# SCH_miniEsp_2025-01-17.net
KiCad netlist of a schematic drawn in EasyEDA
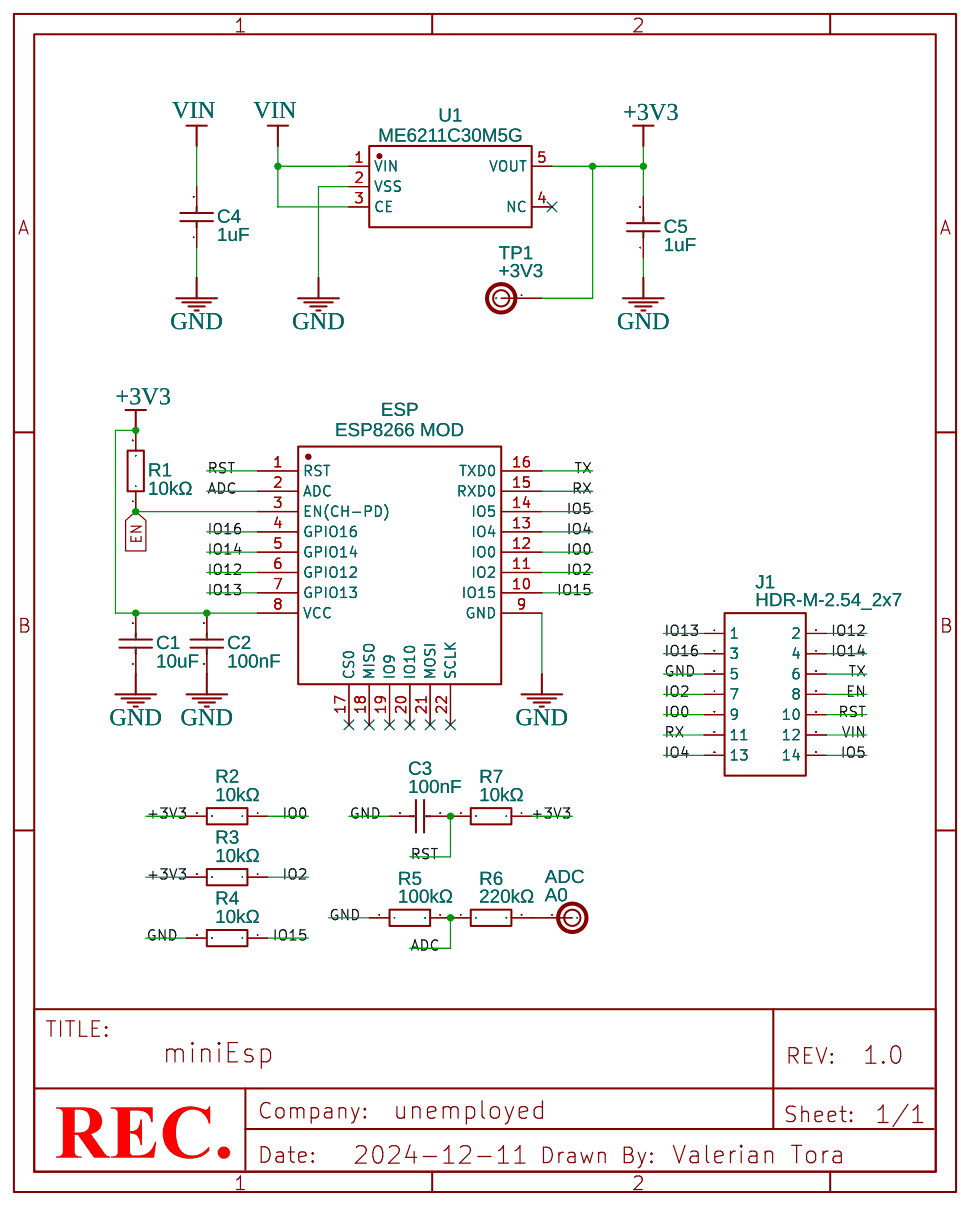
[diagram p0: schematic sheet]

(export (version "E")
  (design (tool "Eeschema 10.0.6"))
  (components
    (comp (ref "ADC") (value "A0") (libsource (lib "") (part "Test Point")))
    (comp (ref "C1")
      (value "10uF")
      (fields
        (field (name "Manufacturer Part") "CL21A106KPFNNNE")
        (field (name "Manufacturer") "SAMSUNG(三星)")
      )
      (libsource (lib "") (part "CL21A106KPFNNNE"))
    )
    (comp (ref "C2")
      (value "100nF")
      (fields
        (field (name "Manufacturer Part") "CL21B104KBCNNNC")
        (field (name "Manufacturer") "SAMSUNG(三星)")
      )
      (libsource (lib "") (part "CL21B104KBCNNNC"))
    )
    (comp (ref "C3")
      (value "100nF")
      (fields
        (field (name "Manufacturer Part") "CL21B104KBCNNNC")
        (field (name "Manufacturer") "SAMSUNG(三星)")
      )
      (libsource (lib "") (part "CL21B104KBCNNNC_1"))
    )
    (comp (ref "C4")
      (value "1uF")
      (fields
        (field (name "Manufacturer Part") "CL21B105KBFNNNE")
        (field (name "Manufacturer") "SAMSUNG(三星)")
      )
      (libsource (lib "") (part "CL21B105KBFNNNE"))
    )
    (comp (ref "C5")
      (value "1uF")
      (fields
        (field (name "Manufacturer Part") "CL21B105KBFNNNE")
        (field (name "Manufacturer") "SAMSUNG(三星)")
      )
      (libsource (lib "") (part "CL21B105KBFNNNE"))
    )
    (comp (ref "ESP")
      (value "ESP8266 MOD")
      (fields
        (field (name "Manufacturer Part") "ESP-12F(ESP8266MOD)")
        (field (name "Manufacturer") "Ai-Thinker(安信可)")
      )
      (libsource (lib "") (part "ESP8266 12F"))
    )
    (comp (ref "J1") (value "HDR-M-2.54_2x7") (libsource (lib "") (part "HDR-M-2.54_2x7")))
    (comp (ref "R1")
      (value "10kΩ")
      (fields (field (name "Manufacturer Part") "AC0603FR-0710KL") (field (name "Manufacturer") "YAGEO(国巨)"))
      (libsource (lib "") (part "AC0603FR-0710KL_1"))
    )
    (comp (ref "R2")
      (value "10kΩ")
      (fields (field (name "Manufacturer Part") "AC0603FR-0710KL") (field (name "Manufacturer") "YAGEO(国巨)"))
      (libsource (lib "") (part "AC0603FR-0710KL"))
    )
    (comp (ref "R3")
      (value "10kΩ")
      (fields (field (name "Manufacturer Part") "AC0603FR-0710KL") (field (name "Manufacturer") "YAGEO(国巨)"))
      (libsource (lib "") (part "AC0603FR-0710KL"))
    )
    (comp (ref "R4")
      (value "10kΩ")
      (fields (field (name "Manufacturer Part") "AC0603FR-0710KL") (field (name "Manufacturer") "YAGEO(国巨)"))
      (libsource (lib "") (part "AC0603FR-0710KL"))
    )
    (comp (ref "R5")
      (value "100kΩ")
      (fields (field (name "Manufacturer Part") "RC0603FR-07100KL") (field (name "Manufacturer") "YAGEO(国巨)"))
      (libsource (lib "") (part "RC0603FR-07100KL"))
    )
    (comp (ref "R6")
      (value "220kΩ")
      (fields (field (name "Manufacturer Part") "RC0603FR-07220KL") (field (name "Manufacturer") "YAGEO(国巨)"))
      (libsource (lib "") (part "RC0603FR-07220KL"))
    )
    (comp (ref "R7")
      (value "10kΩ")
      (fields (field (name "Manufacturer Part") "AC0603FR-0710KL") (field (name "Manufacturer") "YAGEO(国巨)"))
      (libsource (lib "") (part "AC0603FR-0710KL"))
    )
    (comp (ref "TP1") (value "+3V3") (libsource (lib "") (part "Test Point_1")))
    (comp (ref "U1")
      (value "ME6211C30M5G")
      (fields (field (name "Manufacturer") "MICRONE(南京微盟)"))
      (libsource (lib "") (part "ME6211C30M5G"))
    )
  )
  (nets
    (net (code "1") (name "+3V3") (class "Default")
      (node (ref "C1") (pin "2") (pinfunction "2_2") (pintype "input"))
      (node (ref "C2") (pin "2") (pinfunction "2_2") (pintype "input"))
      (node (ref "C5") (pin "2") (pinfunction "2_2") (pintype "input"))
      (node (ref "ESP") (pin "8") (pinfunction "VCC_8") (pintype "unspecified"))
      (node (ref "R1") (pin "2") (pinfunction "2_2") (pintype "input"))
      (node (ref "R2") (pin "2") (pinfunction "2_2") (pintype "input"))
      (node (ref "R3") (pin "2") (pinfunction "2_2") (pintype "input"))
      (node (ref "R7") (pin "1") (pinfunction "1_1") (pintype "input"))
      (node (ref "TP1") (pin "1") (pinfunction "1_1") (pintype "output"))
      (node (ref "U1") (pin "5") (pinfunction "VOUT_5") (pintype "unspecified"))
    )
    (net (code "2") (name "/ADC") (class "Default")
      (node (ref "ESP") (pin "2") (pinfunction "ADC_2") (pintype "unspecified"))
      (node (ref "R5") (pin "2") (pinfunction "2_2") (pintype "unspecified"))
      (node (ref "R6") (pin "1") (pinfunction "1_1") (pintype "input"))
    )
    (net (code "3") (name "/IO0") (class "Default")
      (node (ref "ESP") (pin "12") (pinfunction "IO0_12") (pintype "unspecified"))
      (node (ref "J1") (pin "9") (pinfunction "9_9") (pintype "input"))
      (node (ref "R2") (pin "1") (pinfunction "1_1") (pintype "input"))
    )
    (net (code "4") (name "/IO2") (class "Default")
      (node (ref "ESP") (pin "11") (pinfunction "IO2_11") (pintype "unspecified"))
      (node (ref "J1") (pin "7") (pinfunction "7_7") (pintype "input"))
      (node (ref "R3") (pin "1") (pinfunction "1_1") (pintype "input"))
    )
    (net (code "5") (name "/IO4") (class "Default")
      (node (ref "ESP") (pin "13") (pinfunction "IO4_13") (pintype "unspecified"))
      (node (ref "J1") (pin "13") (pinfunction "13_13") (pintype "input"))
    )
    (net (code "6") (name "/IO5") (class "Default")
      (node (ref "ESP") (pin "14") (pinfunction "IO5_14") (pintype "unspecified"))
      (node (ref "J1") (pin "14") (pinfunction "14_14") (pintype "input"))
    )
    (net (code "7") (name "/IO12") (class "Default")
      (node (ref "ESP") (pin "6") (pinfunction "GPIO12_6") (pintype "unspecified"))
      (node (ref "J1") (pin "2") (pinfunction "2_2") (pintype "input"))
    )
    (net (code "8") (name "/IO13") (class "Default")
      (node (ref "ESP") (pin "7") (pinfunction "GPIO13_7") (pintype "unspecified"))
      (node (ref "J1") (pin "1") (pinfunction "1_1") (pintype "input"))
    )
    (net (code "9") (name "/IO14") (class "Default")
      (node (ref "ESP") (pin "5") (pinfunction "GPIO14_5") (pintype "unspecified"))
      (node (ref "J1") (pin "4") (pinfunction "4_4") (pintype "input"))
    )
    (net (code "10") (name "/IO15") (class "Default")
      (node (ref "ESP") (pin "10") (pinfunction "IO15_10") (pintype "unspecified"))
      (node (ref "R4") (pin "1") (pinfunction "1_1") (pintype "input"))
    )
    (net (code "11") (name "/IO16") (class "Default")
      (node (ref "ESP") (pin "4") (pinfunction "GPIO16_4") (pintype "unspecified"))
      (node (ref "J1") (pin "3") (pinfunction "3_3") (pintype "input"))
    )
    (net (code "12") (name "/RST") (class "Default")
      (node (ref "C3") (pin "1") (pinfunction "1_1") (pintype "input"))
      (node (ref "ESP") (pin "1") (pinfunction "RST_1") (pintype "unspecified"))
      (node (ref "J1") (pin "10") (pinfunction "10_10") (pintype "input"))
      (node (ref "R7") (pin "2") (pinfunction "2_2") (pintype "input"))
    )
    (net (code "13") (name "/RX") (class "Default")
      (node (ref "ESP") (pin "15") (pinfunction "RXD0_15") (pintype "unspecified"))
      (node (ref "J1") (pin "11") (pinfunction "11_11") (pintype "input"))
    )
    (net (code "14") (name "/TX") (class "Default")
      (node (ref "ESP") (pin "16") (pinfunction "TXD0_16") (pintype "unspecified"))
      (node (ref "J1") (pin "6") (pinfunction "6_6") (pintype "input"))
    )
    (net (code "15") (name "EN") (class "Default")
      (node (ref "ESP") (pin "3") (pinfunction "EN(CH-PD)_3") (pintype "unspecified"))
      (node (ref "J1") (pin "8") (pinfunction "8_8") (pintype "input"))
      (node (ref "R1") (pin "1") (pinfunction "1_1") (pintype "input"))
    )
    (net (code "16") (name "GND") (class "Default")
      (node (ref "C1") (pin "1") (pinfunction "1_1") (pintype "input"))
      (node (ref "C2") (pin "1") (pinfunction "1_1") (pintype "input"))
      (node (ref "C3") (pin "2") (pinfunction "2_2") (pintype "input"))
      (node (ref "C4") (pin "1") (pinfunction "1_1") (pintype "input"))
      (node (ref "C5") (pin "1") (pinfunction "1_1") (pintype "input"))
      (node (ref "ESP") (pin "9") (pinfunction "GND_9") (pintype "unspecified"))
      (node (ref "J1") (pin "5") (pinfunction "5_5") (pintype "input"))
      (node (ref "R4") (pin "2") (pinfunction "2_2") (pintype "input"))
      (node (ref "R5") (pin "1") (pinfunction "1_1") (pintype "unspecified"))
      (node (ref "U1") (pin "2") (pinfunction "VSS_2") (pintype "unspecified"))
    )
    (net (code "17") (name "Net-(ADC-Pad1)") (class "Default")
      (node (ref "ADC") (pin "1") (pinfunction "1_1") (pintype "output"))
      (node (ref "R6") (pin "2") (pinfunction "2_2") (pintype "input"))
    )
    (net (code "18") (name "VIN") (class "Default")
      (node (ref "C4") (pin "2") (pinfunction "2_2") (pintype "input"))
      (node (ref "J1") (pin "12") (pinfunction "12_12") (pintype "input"))
      (node (ref "U1") (pin "1") (pinfunction "VIN_1") (pintype "unspecified"))
      (node (ref "U1") (pin "3") (pinfunction "CE_3") (pintype "unspecified"))
    )
    (net (code "19") (name "unconnected-(ESP-CS0-Pad17)") (class "Default")
      (node (ref "ESP") (pin "17") (pinfunction "CS0_17") (pintype "unspecified+no_connect"))
    )
    (net (code "20") (name "unconnected-(ESP-IO9-Pad19)") (class "Default")
      (node (ref "ESP") (pin "19") (pinfunction "IO9_19") (pintype "unspecified+no_connect"))
    )
    (net (code "21") (name "unconnected-(ESP-IO10-Pad20)") (class "Default")
      (node (ref "ESP") (pin "20") (pinfunction "IO10_20") (pintype "unspecified+no_connect"))
    )
    (net (code "22") (name "unconnected-(ESP-MISO-Pad18)") (class "Default")
      (node (ref "ESP") (pin "18") (pinfunction "MISO_18") (pintype "unspecified+no_connect"))
    )
    (net (code "23") (name "unconnected-(ESP-MOSI-Pad21)") (class "Default")
      (node (ref "ESP") (pin "21") (pinfunction "MOSI_21") (pintype "unspecified+no_connect"))
    )
    (net (code "24") (name "unconnected-(ESP-SCLK-Pad22)") (class "Default")
      (node (ref "ESP") (pin "22") (pinfunction "SCLK_22") (pintype "unspecified+no_connect"))
    )
    (net (code "25") (name "unconnected-(U1-NC-Pad4)") (class "Default")
      (node (ref "U1") (pin "4") (pinfunction "NC_4") (pintype "unspecified+no_connect"))
    )
  )
)
